# Sheet1.net
KiCad netlist of a schematic drawn in Altium Designer
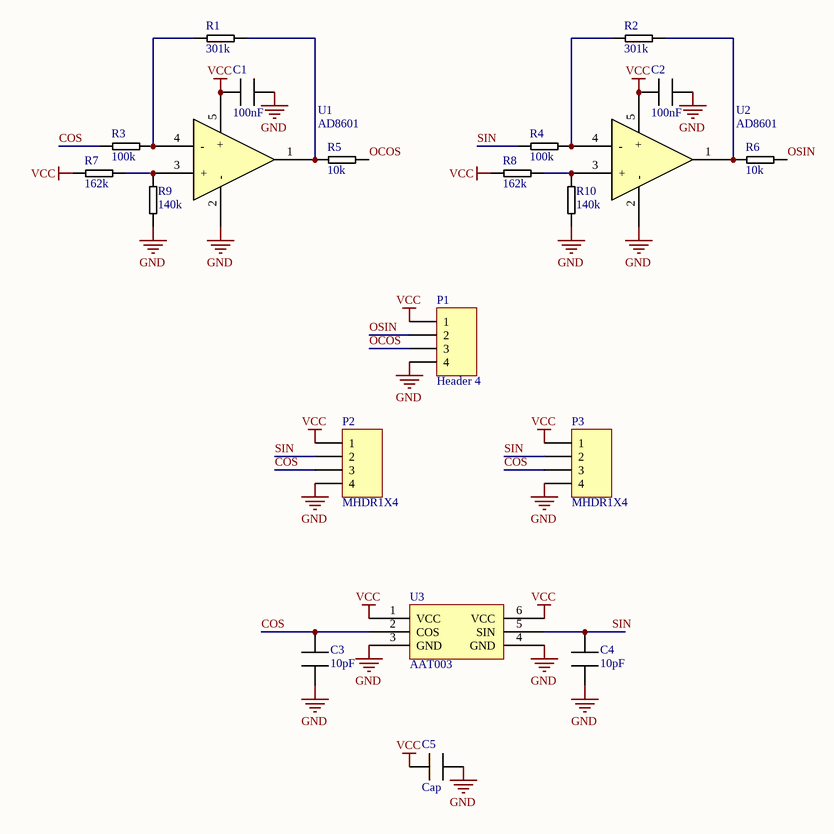
[diagram p0: Sheet1.SchDoc]

(export (version "E")
  (design (tool "Eeschema 10.0.6"))
  (components
    (comp (ref "C1") (value "100nF") (footprint "0603") (libsource (lib "LibCfrpg") (part "Cap")))
    (comp (ref "C2") (value "100nF") (footprint "0603") (libsource (lib "LibCfrpg") (part "Cap")))
    (comp (ref "C3") (value "10pF") (footprint "0603") (libsource (lib "LibCfrpg") (part "Cap")))
    (comp (ref "C4") (value "10pF") (footprint "0603") (libsource (lib "LibCfrpg") (part "Cap")))
    (comp (ref "C5") (value "Cap") (footprint "0603") (libsource (lib "LibCfrpg") (part "Cap")))
    (comp (ref "P1")
      (value "Header 4")
      (footprint "HDR1X4")
      (description "Header, 4-Pin")
      (fields (field (name "PUBLISHER") "Altium Limited"))
      (libsource (lib "Miscellaneous Connectors") (part "Header 4"))
    )
    (comp (ref "P2")
      (value "MHDR1X4")
      (footprint "MHDR1X4")
      (description "Header, 4-Pin")
      (fields (field (name "PUBLISHER") "Altium Limited"))
      (libsource (lib "Miscellaneous Connectors") (part "MHDR1X4"))
    )
    (comp (ref "P3")
      (value "MHDR1X4")
      (footprint "MHDR1X4")
      (description "Header, 4-Pin")
      (fields (field (name "PUBLISHER") "Altium Limited"))
      (libsource (lib "Miscellaneous Connectors") (part "MHDR1X4"))
    )
    (comp (ref "R1") (value "301k") (footprint "0603") (libsource (lib "LibCfrpg") (part "Res")))
    (comp (ref "R2") (value "301k") (footprint "0603") (libsource (lib "LibCfrpg") (part "Res")))
    (comp (ref "R3") (value "100k") (footprint "0603") (libsource (lib "LibCfrpg") (part "Res")))
    (comp (ref "R4") (value "100k") (footprint "0603") (libsource (lib "LibCfrpg") (part "Res")))
    (comp (ref "R5") (value "10k") (footprint "0603") (libsource (lib "LibCfrpg") (part "Res")))
    (comp (ref "R6") (value "10k") (footprint "0603") (libsource (lib "LibCfrpg") (part "Res")))
    (comp (ref "R7") (value "162k") (footprint "0603") (libsource (lib "LibCfrpg") (part "Res")))
    (comp (ref "R8") (value "162k") (footprint "0603") (libsource (lib "LibCfrpg") (part "Res")))
    (comp (ref "R9") (value "140k") (footprint "0603") (libsource (lib "LibCfrpg") (part "Res")))
    (comp (ref "R10") (value "140k") (footprint "0603") (libsource (lib "LibCfrpg") (part "Res")))
    (comp (ref "U1") (value "AD8601") (footprint "SOT23-5") (libsource (lib "LibCfrpg") (part "AD8601")))
    (comp (ref "U2") (value "AD8601") (footprint "SOT23-5") (libsource (lib "LibCfrpg") (part "AD8601")))
    (comp (ref "U3")
      (value "AAT003")
      (footprint "PSON65P250X80_HS-7M")
      (libsource (lib "LibCfrpg") (part "AAT003"))
    )
  )
  (nets
    (net (code "1") (name "/COS") (class "Default")
      (node (ref "C3") (pin "2") (pintype "passive"))
      (node (ref "P2") (pin "3") (pinfunction "3_3") (pintype "passive"))
      (node (ref "P3") (pin "3") (pinfunction "3_3") (pintype "passive"))
      (node (ref "R3") (pin "1") (pintype "passive"))
      (node (ref "U3") (pin "2") (pinfunction "COS_2") (pintype "passive"))
    )
    (net (code "2") (name "/OCOS") (class "Default")
      (node (ref "P1") (pin "3") (pinfunction "3_3") (pintype "passive"))
      (node (ref "R5") (pin "2") (pintype "passive"))
    )
    (net (code "3") (name "/OSIN") (class "Default")
      (node (ref "P1") (pin "2") (pinfunction "2_2") (pintype "passive"))
      (node (ref "R6") (pin "2") (pintype "passive"))
    )
    (net (code "4") (name "/SIN") (class "Default")
      (node (ref "C4") (pin "2") (pintype "passive"))
      (node (ref "P2") (pin "2") (pinfunction "2_2") (pintype "passive"))
      (node (ref "P3") (pin "2") (pinfunction "2_2") (pintype "passive"))
      (node (ref "R4") (pin "1") (pintype "passive"))
      (node (ref "U3") (pin "5") (pinfunction "SIN_5") (pintype "passive"))
    )
    (net (code "5") (name "GND") (class "Default")
      (node (ref "C1") (pin "2") (pintype "passive"))
      (node (ref "C2") (pin "2") (pintype "passive"))
      (node (ref "C3") (pin "1") (pintype "passive"))
      (node (ref "C4") (pin "1") (pintype "passive"))
      (node (ref "C5") (pin "2") (pintype "passive"))
      (node (ref "P1") (pin "4") (pinfunction "4_4") (pintype "passive"))
      (node (ref "P2") (pin "4") (pinfunction "4_4") (pintype "passive"))
      (node (ref "P3") (pin "4") (pinfunction "4_4") (pintype "passive"))
      (node (ref "R10") (pin "1") (pintype "passive"))
      (node (ref "R9") (pin "1") (pintype "passive"))
      (node (ref "U1") (pin "2") (pinfunction "-_2") (pintype "passive"))
      (node (ref "U2") (pin "2") (pinfunction "-_2") (pintype "passive"))
      (node (ref "U3") (pin "3") (pinfunction "GND_3") (pintype "passive"))
      (node (ref "U3") (pin "4") (pinfunction "GND_4") (pintype "passive"))
    )
    (net (code "6") (name "Net-(R1-Pad1)") (class "Default")
      (node (ref "R1") (pin "1") (pintype "passive"))
      (node (ref "R3") (pin "2") (pintype "passive"))
      (node (ref "U1") (pin "4") (pinfunction "-_4") (pintype "passive"))
    )
    (net (code "7") (name "Net-(R1-Pad2)") (class "Default")
      (node (ref "R1") (pin "2") (pintype "passive"))
      (node (ref "R5") (pin "1") (pintype "passive"))
      (node (ref "U1") (pin "1") (pintype "passive"))
    )
    (net (code "8") (name "Net-(R2-Pad1)") (class "Default")
      (node (ref "R2") (pin "1") (pintype "passive"))
      (node (ref "R4") (pin "2") (pintype "passive"))
      (node (ref "U2") (pin "4") (pinfunction "-_4") (pintype "passive"))
    )
    (net (code "9") (name "Net-(R2-Pad2)") (class "Default")
      (node (ref "R2") (pin "2") (pintype "passive"))
      (node (ref "R6") (pin "1") (pintype "passive"))
      (node (ref "U2") (pin "1") (pintype "passive"))
    )
    (net (code "10") (name "Net-(R7-Pad2)") (class "Default")
      (node (ref "R7") (pin "2") (pintype "passive"))
      (node (ref "R9") (pin "2") (pintype "passive"))
      (node (ref "U1") (pin "3") (pinfunction "+_3") (pintype "passive"))
    )
    (net (code "11") (name "Net-(R10-Pad2)") (class "Default")
      (node (ref "R10") (pin "2") (pintype "passive"))
      (node (ref "R8") (pin "2") (pintype "passive"))
      (node (ref "U2") (pin "3") (pinfunction "+_3") (pintype "passive"))
    )
    (net (code "12") (name "VCC") (class "Default")
      (node (ref "C1") (pin "1") (pintype "passive"))
      (node (ref "C2") (pin "1") (pintype "passive"))
      (node (ref "C5") (pin "1") (pintype "passive"))
      (node (ref "P1") (pin "1") (pinfunction "1_1") (pintype "passive"))
      (node (ref "P2") (pin "1") (pinfunction "1_1") (pintype "passive"))
      (node (ref "P3") (pin "1") (pinfunction "1_1") (pintype "passive"))
      (node (ref "R7") (pin "1") (pintype "passive"))
      (node (ref "R8") (pin "1") (pintype "passive"))
      (node (ref "U1") (pin "5") (pinfunction "+_5") (pintype "passive"))
      (node (ref "U2") (pin "5") (pinfunction "+_5") (pintype "passive"))
      (node (ref "U3") (pin "1") (pinfunction "VCC_1") (pintype "passive"))
      (node (ref "U3") (pin "6") (pinfunction "VCC_6") (pintype "passive"))
    )
  )
)
